# printer_control.net
KiCad netlist of a schematic drawn in Altium Designer
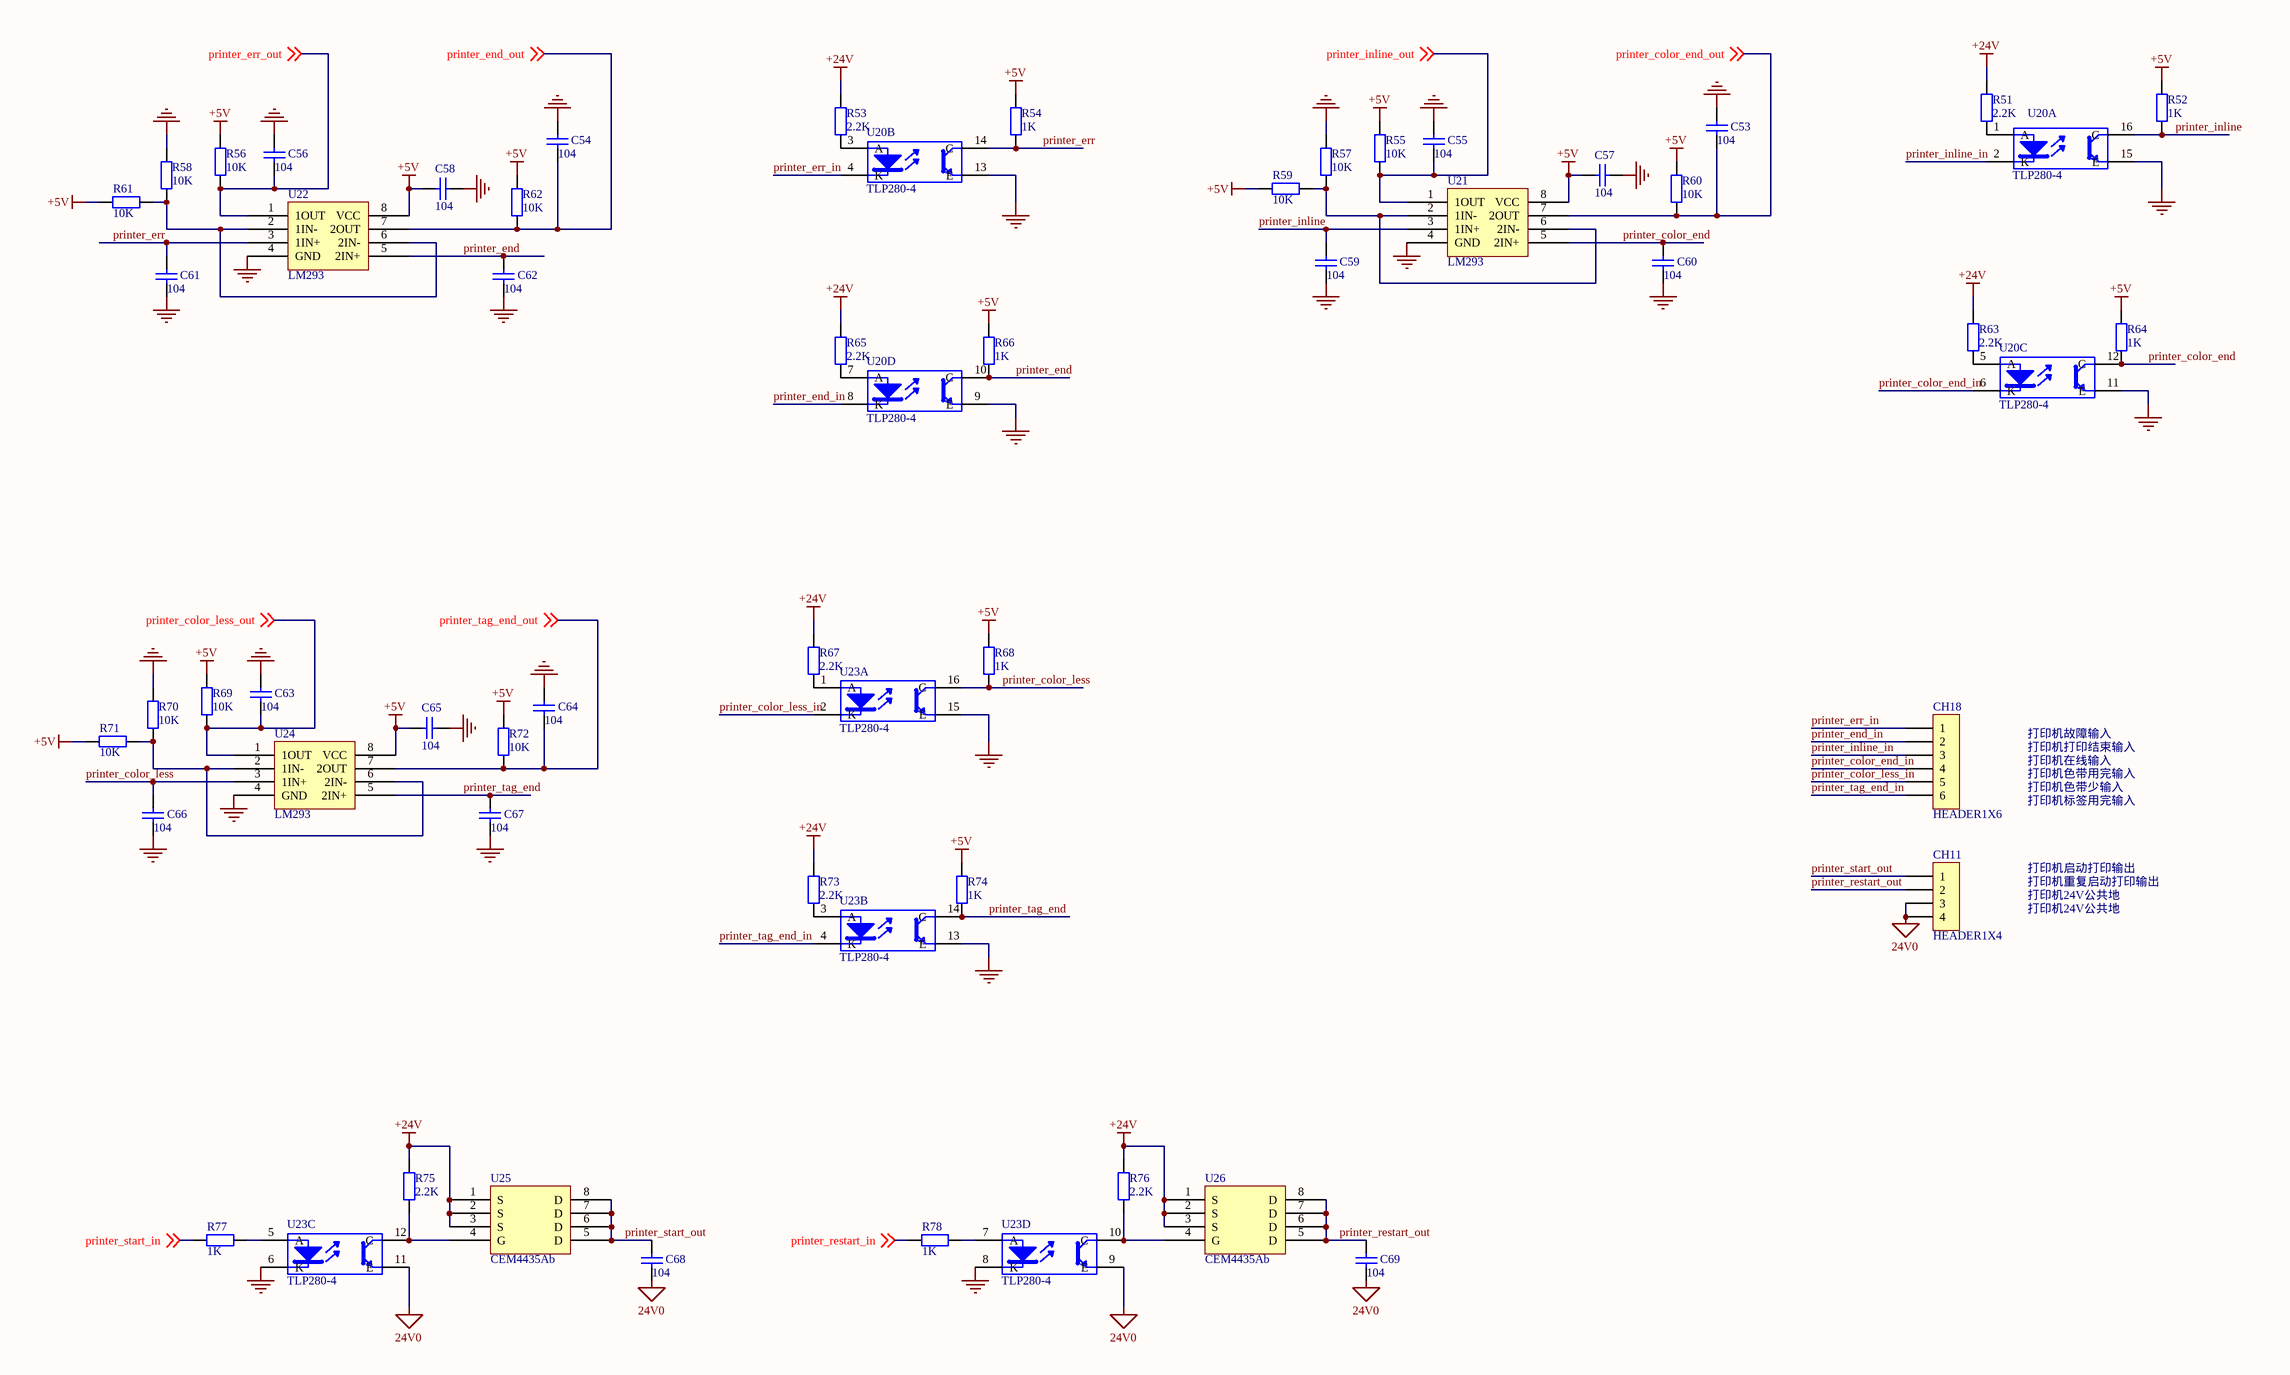
[diagram p0: printer_control.SchDoc]

(export (version "E")
  (design (tool "Eeschema 10.0.6"))
  (components
    (comp (ref "C53")
      (value "104")
      (footprint "0805")
      (description "Capacitor")
      (fields (field (name "Comment") "Cap") (field (name "PUBLISHER") "Altium Limited"))
      (libsource (lib "Miscellaneous Devices") (part "Cap"))
    )
    (comp (ref "C54")
      (value "104")
      (footprint "0805")
      (description "Capacitor")
      (fields (field (name "Comment") "Cap") (field (name "PUBLISHER") "Altium Limited"))
      (libsource (lib "Miscellaneous Devices") (part "Cap"))
    )
    (comp (ref "C55")
      (value "104")
      (footprint "0805")
      (description "Capacitor")
      (fields (field (name "Comment") "Cap") (field (name "PUBLISHER") "Altium Limited"))
      (libsource (lib "Miscellaneous Devices") (part "Cap"))
    )
    (comp (ref "C56")
      (value "104")
      (footprint "0805")
      (description "Capacitor")
      (fields (field (name "Comment") "Cap") (field (name "PUBLISHER") "Altium Limited"))
      (libsource (lib "Miscellaneous Devices") (part "Cap"))
    )
    (comp (ref "C57")
      (value "104")
      (footprint "0805")
      (description "Capacitor")
      (fields (field (name "Comment") "Cap") (field (name "PUBLISHER") "Altium Limited"))
      (libsource (lib "Miscellaneous Devices") (part "Cap"))
    )
    (comp (ref "C58")
      (value "104")
      (footprint "0805")
      (description "Capacitor")
      (fields (field (name "Comment") "Cap") (field (name "PUBLISHER") "Altium Limited"))
      (libsource (lib "Miscellaneous Devices") (part "Cap"))
    )
    (comp (ref "C59")
      (value "104")
      (footprint "0805")
      (description "Capacitor")
      (fields (field (name "Comment") "Cap") (field (name "PUBLISHER") "Altium Limited"))
      (libsource (lib "Miscellaneous Devices") (part "Cap"))
    )
    (comp (ref "C60")
      (value "104")
      (footprint "0805")
      (description "Capacitor")
      (fields (field (name "Comment") "Cap") (field (name "PUBLISHER") "Altium Limited"))
      (libsource (lib "Miscellaneous Devices") (part "Cap"))
    )
    (comp (ref "C61")
      (value "104")
      (footprint "0805")
      (description "Capacitor")
      (fields (field (name "Comment") "Cap") (field (name "PUBLISHER") "Altium Limited"))
      (libsource (lib "Miscellaneous Devices") (part "Cap"))
    )
    (comp (ref "C62")
      (value "104")
      (footprint "0805")
      (description "Capacitor")
      (fields (field (name "Comment") "Cap") (field (name "PUBLISHER") "Altium Limited"))
      (libsource (lib "Miscellaneous Devices") (part "Cap"))
    )
    (comp (ref "C63")
      (value "104")
      (footprint "0805")
      (description "Capacitor")
      (fields (field (name "Comment") "Cap") (field (name "PUBLISHER") "Altium Limited"))
      (libsource (lib "Miscellaneous Devices") (part "Cap"))
    )
    (comp (ref "C64")
      (value "104")
      (footprint "0805")
      (description "Capacitor")
      (fields (field (name "Comment") "Cap") (field (name "PUBLISHER") "Altium Limited"))
      (libsource (lib "Miscellaneous Devices") (part "Cap"))
    )
    (comp (ref "C65")
      (value "104")
      (footprint "0805")
      (description "Capacitor")
      (fields (field (name "Comment") "Cap") (field (name "PUBLISHER") "Altium Limited"))
      (libsource (lib "Miscellaneous Devices") (part "Cap"))
    )
    (comp (ref "C66")
      (value "104")
      (footprint "0805")
      (description "Capacitor")
      (fields (field (name "Comment") "Cap") (field (name "PUBLISHER") "Altium Limited"))
      (libsource (lib "Miscellaneous Devices") (part "Cap"))
    )
    (comp (ref "C67")
      (value "104")
      (footprint "0805")
      (description "Capacitor")
      (fields (field (name "Comment") "Cap") (field (name "PUBLISHER") "Altium Limited"))
      (libsource (lib "Miscellaneous Devices") (part "Cap"))
    )
    (comp (ref "C68")
      (value "104")
      (footprint "0805")
      (description "Capacitor")
      (fields (field (name "Comment") "Capb") (field (name "PUBLISHER") "Altium Limited"))
      (libsource (lib "Miscellaneous Devices") (part "Cap"))
    )
    (comp (ref "C69")
      (value "104")
      (footprint "0805")
      (description "Capacitor")
      (fields (field (name "Comment") "Capb") (field (name "PUBLISHER") "Altium Limited"))
      (libsource (lib "Miscellaneous Devices") (part "Cap"))
    )
    (comp (ref "CH11")
      (value "HEADER1X4")
      (footprint "CH3.96-4PIN")
      (libsource (lib "myIntegrated_Library1") (part "HEADER1X4"))
    )
    (comp (ref "CH18")
      (value "HEADER1X6")
      (footprint "CH3.96-6PIN")
      (libsource (lib "myIntegrated_Library1") (part "HEADER1X6"))
    )
    (comp (ref "R51")
      (value "2.2K")
      (footprint "0805")
      (description "Resistor")
      (fields (field (name "Comment") "Res2") (field (name "PUBLISHER") "Altium Limited"))
      (libsource (lib "") (part "Res2_1"))
    )
    (comp (ref "R52")
      (value "1K")
      (footprint "0805")
      (description "Resistor")
      (fields (field (name "Comment") "Res2") (field (name "PUBLISHER") "Altium Limited"))
      (libsource (lib "") (part "Res2_1"))
    )
    (comp (ref "R53")
      (value "2.2K")
      (footprint "0805")
      (description "Resistor")
      (fields (field (name "Comment") "Res2") (field (name "PUBLISHER") "Altium Limited"))
      (libsource (lib "") (part "Res2_1"))
    )
    (comp (ref "R54")
      (value "1K")
      (footprint "0805")
      (description "Resistor")
      (fields (field (name "Comment") "Res2") (field (name "PUBLISHER") "Altium Limited"))
      (libsource (lib "") (part "Res2_1"))
    )
    (comp (ref "R55")
      (value "10K")
      (footprint "0805")
      (description "Resistor")
      (fields (field (name "Comment") "Res2") (field (name "PUBLISHER") "Altium Limited"))
      (libsource (lib "") (part "Res2_1"))
    )
    (comp (ref "R56")
      (value "10K")
      (footprint "0805")
      (description "Resistor")
      (fields (field (name "Comment") "Res2") (field (name "PUBLISHER") "Altium Limited"))
      (libsource (lib "") (part "Res2_1"))
    )
    (comp (ref "R57")
      (value "10K")
      (footprint "0805")
      (description "Resistor")
      (fields (field (name "Comment") "Res2") (field (name "PUBLISHER") "Altium Limited"))
      (libsource (lib "") (part "Res2_1"))
    )
    (comp (ref "R58")
      (value "10K")
      (footprint "0805")
      (description "Resistor")
      (fields (field (name "Comment") "Res2") (field (name "PUBLISHER") "Altium Limited"))
      (libsource (lib "") (part "Res2_1"))
    )
    (comp (ref "R59")
      (value "10K")
      (footprint "0805")
      (description "Resistor")
      (fields (field (name "Comment") "Res2") (field (name "PUBLISHER") "Altium Limited"))
      (libsource (lib "Miscellaneous Devices") (part "Res2"))
    )
    (comp (ref "R60")
      (value "10K")
      (footprint "0805")
      (description "Resistor")
      (fields (field (name "Comment") "Res2") (field (name "PUBLISHER") "Altium Limited"))
      (libsource (lib "") (part "Res2_1"))
    )
    (comp (ref "R61")
      (value "10K")
      (footprint "0805")
      (description "Resistor")
      (fields (field (name "Comment") "Res2") (field (name "PUBLISHER") "Altium Limited"))
      (libsource (lib "Miscellaneous Devices") (part "Res2"))
    )
    (comp (ref "R62")
      (value "10K")
      (footprint "0805")
      (description "Resistor")
      (fields (field (name "Comment") "Res2") (field (name "PUBLISHER") "Altium Limited"))
      (libsource (lib "") (part "Res2_1"))
    )
    (comp (ref "R63")
      (value "2.2K")
      (footprint "0805")
      (description "Resistor")
      (fields (field (name "Comment") "Res2") (field (name "PUBLISHER") "Altium Limited"))
      (libsource (lib "") (part "Res2_1"))
    )
    (comp (ref "R64")
      (value "1K")
      (footprint "0805")
      (description "Resistor")
      (fields (field (name "Comment") "Res2") (field (name "PUBLISHER") "Altium Limited"))
      (libsource (lib "") (part "Res2_1"))
    )
    (comp (ref "R65")
      (value "2.2K")
      (footprint "0805")
      (description "Resistor")
      (fields (field (name "Comment") "Res2") (field (name "PUBLISHER") "Altium Limited"))
      (libsource (lib "") (part "Res2_1"))
    )
    (comp (ref "R66")
      (value "1K")
      (footprint "0805")
      (description "Resistor")
      (fields (field (name "Comment") "Res2") (field (name "PUBLISHER") "Altium Limited"))
      (libsource (lib "") (part "Res2_1"))
    )
    (comp (ref "R67")
      (value "2.2K")
      (footprint "0805")
      (description "Resistor")
      (fields (field (name "Comment") "Res2") (field (name "PUBLISHER") "Altium Limited"))
      (libsource (lib "") (part "Res2_1"))
    )
    (comp (ref "R68")
      (value "1K")
      (footprint "0805")
      (description "Resistor")
      (fields (field (name "Comment") "Res2") (field (name "PUBLISHER") "Altium Limited"))
      (libsource (lib "") (part "Res2_1"))
    )
    (comp (ref "R69")
      (value "10K")
      (footprint "0805")
      (description "Resistor")
      (fields (field (name "Comment") "Res2") (field (name "PUBLISHER") "Altium Limited"))
      (libsource (lib "") (part "Res2_1"))
    )
    (comp (ref "R70")
      (value "10K")
      (footprint "0805")
      (description "Resistor")
      (fields (field (name "Comment") "Res2") (field (name "PUBLISHER") "Altium Limited"))
      (libsource (lib "") (part "Res2_1"))
    )
    (comp (ref "R71")
      (value "10K")
      (footprint "0805")
      (description "Resistor")
      (fields (field (name "Comment") "Res2") (field (name "PUBLISHER") "Altium Limited"))
      (libsource (lib "Miscellaneous Devices") (part "Res2"))
    )
    (comp (ref "R72")
      (value "10K")
      (footprint "0805")
      (description "Resistor")
      (fields (field (name "Comment") "Res2") (field (name "PUBLISHER") "Altium Limited"))
      (libsource (lib "") (part "Res2_1"))
    )
    (comp (ref "R73")
      (value "2.2K")
      (footprint "0805")
      (description "Resistor")
      (fields (field (name "Comment") "Res2") (field (name "PUBLISHER") "Altium Limited"))
      (libsource (lib "") (part "Res2_1"))
    )
    (comp (ref "R74")
      (value "1K")
      (footprint "0805")
      (description "Resistor")
      (fields (field (name "Comment") "Res2") (field (name "PUBLISHER") "Altium Limited"))
      (libsource (lib "") (part "Res2_1"))
    )
    (comp (ref "R75")
      (value "2.2K")
      (footprint "0805")
      (description "Resistor")
      (fields (field (name "Comment") "Res2") (field (name "PUBLISHER") "Altium Limited"))
      (libsource (lib "") (part "Res2_1"))
    )
    (comp (ref "R76")
      (value "2.2K")
      (footprint "0805")
      (description "Resistor")
      (fields (field (name "Comment") "Res2") (field (name "PUBLISHER") "Altium Limited"))
      (libsource (lib "") (part "Res2_1"))
    )
    (comp (ref "R77")
      (value "1K")
      (footprint "0805")
      (description "Resistor")
      (fields (field (name "Comment") "Res2") (field (name "PUBLISHER") "Altium Limited"))
      (libsource (lib "Miscellaneous Devices") (part "Res2"))
    )
    (comp (ref "R78")
      (value "1K")
      (footprint "0805")
      (description "Resistor")
      (fields (field (name "Comment") "Res2") (field (name "PUBLISHER") "Altium Limited"))
      (libsource (lib "Miscellaneous Devices") (part "Res2"))
    )
    (comp (ref "U20") (value "TLP280-4") (footprint "SO16") (libsource (lib "WH V20") (part "TLP521-4")))
    (comp (ref "U21")
      (value "LM293")
      (footprint "SOP8-OP27")
      (libsource (lib "myIntegrated_Library1") (part "LM293"))
    )
    (comp (ref "U22")
      (value "LM293")
      (footprint "SOP8-OP27")
      (libsource (lib "myIntegrated_Library1") (part "LM293"))
    )
    (comp (ref "U23") (value "TLP280-4") (footprint "SO16") (libsource (lib "WH V20") (part "TLP521-4")))
    (comp (ref "U24")
      (value "LM293")
      (footprint "SOP8-OP27")
      (libsource (lib "myIntegrated_Library1") (part "LM293"))
    )
    (comp (ref "U25")
      (value "CEM4435Ab")
      (footprint "SOP8-OP27")
      (libsource (lib "myIntegrated_Library1") (part "CEM4435A"))
    )
    (comp (ref "U26")
      (value "CEM4435Ab")
      (footprint "SOP8-OP27")
      (libsource (lib "myIntegrated_Library1") (part "CEM4435A"))
    )
  )
  (nets
    (net (code "1") (name "+5V") (class "Default")
      (node (ref "C57") (pin "2") (pinfunction "2_2") (pintype "passive"))
      (node (ref "C58") (pin "2") (pinfunction "2_2") (pintype "passive"))
      (node (ref "C65") (pin "2") (pinfunction "2_2") (pintype "passive"))
      (node (ref "R52") (pin "1") (pinfunction "1_1") (pintype "passive"))
      (node (ref "R54") (pin "1") (pinfunction "1_1") (pintype "passive"))
      (node (ref "R55") (pin "1") (pinfunction "1_1") (pintype "passive"))
      (node (ref "R56") (pin "1") (pinfunction "1_1") (pintype "passive"))
      (node (ref "R59") (pin "1") (pinfunction "1_1") (pintype "passive"))
      (node (ref "R60") (pin "1") (pinfunction "1_1") (pintype "passive"))
      (node (ref "R61") (pin "1") (pinfunction "1_1") (pintype "passive"))
      (node (ref "R62") (pin "1") (pinfunction "1_1") (pintype "passive"))
      (node (ref "R64") (pin "1") (pinfunction "1_1") (pintype "passive"))
      (node (ref "R66") (pin "1") (pinfunction "1_1") (pintype "passive"))
      (node (ref "R68") (pin "1") (pinfunction "1_1") (pintype "passive"))
      (node (ref "R69") (pin "1") (pinfunction "1_1") (pintype "passive"))
      (node (ref "R71") (pin "1") (pinfunction "1_1") (pintype "passive"))
      (node (ref "R72") (pin "1") (pinfunction "1_1") (pintype "passive"))
      (node (ref "R74") (pin "1") (pinfunction "1_1") (pintype "passive"))
      (node (ref "U21") (pin "8") (pinfunction "VCC_8") (pintype "passive"))
      (node (ref "U22") (pin "8") (pinfunction "VCC_8") (pintype "passive"))
      (node (ref "U24") (pin "8") (pinfunction "VCC_8") (pintype "passive"))
    )
    (net (code "2") (name "+24V") (class "Default")
      (node (ref "R51") (pin "1") (pinfunction "1_1") (pintype "passive"))
      (node (ref "R53") (pin "1") (pinfunction "1_1") (pintype "passive"))
      (node (ref "R63") (pin "1") (pinfunction "1_1") (pintype "passive"))
      (node (ref "R65") (pin "1") (pinfunction "1_1") (pintype "passive"))
      (node (ref "R67") (pin "1") (pinfunction "1_1") (pintype "passive"))
      (node (ref "R73") (pin "1") (pinfunction "1_1") (pintype "passive"))
      (node (ref "R75") (pin "1") (pinfunction "1_1") (pintype "passive"))
      (node (ref "R76") (pin "1") (pinfunction "1_1") (pintype "passive"))
      (node (ref "U25") (pin "1") (pinfunction "S_1") (pintype "passive"))
      (node (ref "U25") (pin "2") (pinfunction "S_2") (pintype "passive"))
      (node (ref "U25") (pin "3") (pinfunction "S_3") (pintype "passive"))
      (node (ref "U26") (pin "1") (pinfunction "S_1") (pintype "passive"))
      (node (ref "U26") (pin "2") (pinfunction "S_2") (pintype "passive"))
      (node (ref "U26") (pin "3") (pinfunction "S_3") (pintype "passive"))
    )
    (net (code "3") (name "/printer_color_end") (class "Default")
      (node (ref "C60") (pin "2") (pinfunction "2_2") (pintype "passive"))
      (node (ref "R64") (pin "2") (pinfunction "2_2") (pintype "passive"))
      (node (ref "U20") (pin "12") (pinfunction "C_12") (pintype "passive"))
      (node (ref "U21") (pin "5") (pinfunction "2IN+_5") (pintype "passive"))
    )
    (net (code "4") (name "/printer_color_end_in") (class "Default")
      (node (ref "CH18") (pin "4") (pinfunction "4_4") (pintype "passive"))
      (node (ref "U20") (pin "6") (pinfunction "K_6") (pintype "passive"))
    )
    (net (code "5") (name "/printer_color_less") (class "Default")
      (node (ref "C66") (pin "2") (pinfunction "2_2") (pintype "passive"))
      (node (ref "R68") (pin "2") (pinfunction "2_2") (pintype "passive"))
      (node (ref "U23") (pin "16") (pinfunction "C_16") (pintype "passive"))
      (node (ref "U24") (pin "3") (pinfunction "1IN+_3") (pintype "passive"))
    )
    (net (code "6") (name "/printer_color_less_in") (class "Default")
      (node (ref "CH18") (pin "5") (pinfunction "5_5") (pintype "passive"))
      (node (ref "U23") (pin "2") (pinfunction "K_2") (pintype "passive"))
    )
    (net (code "7") (name "/printer_end") (class "Default")
      (node (ref "C62") (pin "2") (pinfunction "2_2") (pintype "passive"))
      (node (ref "R66") (pin "2") (pinfunction "2_2") (pintype "passive"))
      (node (ref "U20") (pin "10") (pinfunction "C_10") (pintype "passive"))
      (node (ref "U22") (pin "5") (pinfunction "2IN+_5") (pintype "passive"))
    )
    (net (code "8") (name "/printer_end_in") (class "Default")
      (node (ref "CH18") (pin "2") (pinfunction "2_2") (pintype "passive"))
      (node (ref "U20") (pin "8") (pinfunction "K_8") (pintype "passive"))
    )
    (net (code "9") (name "/printer_err") (class "Default")
      (node (ref "C61") (pin "2") (pinfunction "2_2") (pintype "passive"))
      (node (ref "R54") (pin "2") (pinfunction "2_2") (pintype "passive"))
      (node (ref "U20") (pin "14") (pinfunction "C_14") (pintype "passive"))
      (node (ref "U22") (pin "3") (pinfunction "1IN+_3") (pintype "passive"))
    )
    (net (code "10") (name "/printer_err_in") (class "Default")
      (node (ref "CH18") (pin "1") (pinfunction "1_1") (pintype "passive"))
      (node (ref "U20") (pin "4") (pinfunction "K_4") (pintype "passive"))
    )
    (net (code "11") (name "/printer_inline") (class "Default")
      (node (ref "C59") (pin "2") (pinfunction "2_2") (pintype "passive"))
      (node (ref "R52") (pin "2") (pinfunction "2_2") (pintype "passive"))
      (node (ref "U20") (pin "16") (pinfunction "C_16") (pintype "passive"))
      (node (ref "U21") (pin "3") (pinfunction "1IN+_3") (pintype "passive"))
    )
    (net (code "12") (name "/printer_inline_in") (class "Default")
      (node (ref "CH18") (pin "3") (pinfunction "3_3") (pintype "passive"))
      (node (ref "U20") (pin "2") (pinfunction "K_2") (pintype "passive"))
    )
    (net (code "13") (name "/printer_restart_out") (class "Default")
      (node (ref "C69") (pin "2") (pinfunction "2_2") (pintype "passive"))
      (node (ref "CH11") (pin "2") (pinfunction "2_2") (pintype "passive"))
      (node (ref "U26") (pin "5") (pinfunction "D_5") (pintype "passive"))
      (node (ref "U26") (pin "6") (pinfunction "D_6") (pintype "passive"))
      (node (ref "U26") (pin "7") (pinfunction "D_7") (pintype "passive"))
      (node (ref "U26") (pin "8") (pinfunction "D_8") (pintype "passive"))
    )
    (net (code "14") (name "/printer_start_out") (class "Default")
      (node (ref "C68") (pin "2") (pinfunction "2_2") (pintype "passive"))
      (node (ref "CH11") (pin "1") (pinfunction "1_1") (pintype "passive"))
      (node (ref "U25") (pin "5") (pinfunction "D_5") (pintype "passive"))
      (node (ref "U25") (pin "6") (pinfunction "D_6") (pintype "passive"))
      (node (ref "U25") (pin "7") (pinfunction "D_7") (pintype "passive"))
      (node (ref "U25") (pin "8") (pinfunction "D_8") (pintype "passive"))
    )
    (net (code "15") (name "/printer_tag_end") (class "Default")
      (node (ref "C67") (pin "2") (pinfunction "2_2") (pintype "passive"))
      (node (ref "R74") (pin "2") (pinfunction "2_2") (pintype "passive"))
      (node (ref "U23") (pin "14") (pinfunction "C_14") (pintype "passive"))
      (node (ref "U24") (pin "5") (pinfunction "2IN+_5") (pintype "passive"))
    )
    (net (code "16") (name "/printer_tag_end_in") (class "Default")
      (node (ref "CH18") (pin "6") (pinfunction "6_6") (pintype "passive"))
      (node (ref "U23") (pin "4") (pinfunction "K_4") (pintype "passive"))
    )
    (net (code "17") (name "24V0") (class "Default")
      (node (ref "C68") (pin "1") (pinfunction "1_1") (pintype "passive"))
      (node (ref "C69") (pin "1") (pinfunction "1_1") (pintype "passive"))
      (node (ref "CH11") (pin "3") (pinfunction "3_3") (pintype "passive"))
      (node (ref "CH11") (pin "4") (pinfunction "4_4") (pintype "passive"))
      (node (ref "U23") (pin "11") (pinfunction "E_11") (pintype "passive"))
      (node (ref "U23") (pin "9") (pinfunction "E_9") (pintype "passive"))
    )
    (net (code "18") (name "GND") (class "Default")
      (node (ref "C53") (pin "2") (pinfunction "2_2") (pintype "passive"))
      (node (ref "C54") (pin "2") (pinfunction "2_2") (pintype "passive"))
      (node (ref "C55") (pin "2") (pinfunction "2_2") (pintype "passive"))
      (node (ref "C56") (pin "2") (pinfunction "2_2") (pintype "passive"))
      (node (ref "C57") (pin "1") (pinfunction "1_1") (pintype "passive"))
      (node (ref "C58") (pin "1") (pinfunction "1_1") (pintype "passive"))
      (node (ref "C59") (pin "1") (pinfunction "1_1") (pintype "passive"))
      (node (ref "C60") (pin "1") (pinfunction "1_1") (pintype "passive"))
      (node (ref "C61") (pin "1") (pinfunction "1_1") (pintype "passive"))
      (node (ref "C62") (pin "1") (pinfunction "1_1") (pintype "passive"))
      (node (ref "C63") (pin "2") (pinfunction "2_2") (pintype "passive"))
      (node (ref "C64") (pin "2") (pinfunction "2_2") (pintype "passive"))
      (node (ref "C65") (pin "1") (pinfunction "1_1") (pintype "passive"))
      (node (ref "C66") (pin "1") (pinfunction "1_1") (pintype "passive"))
      (node (ref "C67") (pin "1") (pinfunction "1_1") (pintype "passive"))
      (node (ref "R57") (pin "1") (pinfunction "1_1") (pintype "passive"))
      (node (ref "R58") (pin "1") (pinfunction "1_1") (pintype "passive"))
      (node (ref "R70") (pin "1") (pinfunction "1_1") (pintype "passive"))
      (node (ref "U20") (pin "11") (pinfunction "E_11") (pintype "passive"))
      (node (ref "U20") (pin "13") (pinfunction "E_13") (pintype "passive"))
      (node (ref "U20") (pin "15") (pinfunction "E_15") (pintype "passive"))
      (node (ref "U20") (pin "9") (pinfunction "E_9") (pintype "passive"))
      (node (ref "U21") (pin "4") (pinfunction "GND_4") (pintype "passive"))
      (node (ref "U22") (pin "4") (pinfunction "GND_4") (pintype "passive"))
      (node (ref "U23") (pin "13") (pinfunction "E_13") (pintype "passive"))
      (node (ref "U23") (pin "15") (pinfunction "E_15") (pintype "passive"))
      (node (ref "U23") (pin "6") (pinfunction "K_6") (pintype "passive"))
      (node (ref "U23") (pin "8") (pinfunction "K_8") (pintype "passive"))
      (node (ref "U24") (pin "4") (pinfunction "GND_4") (pintype "passive"))
    )
    (net (code "19") (name "Net-(U20A-A)") (class "Default")
      (node (ref "R51") (pin "2") (pinfunction "2_2") (pintype "passive"))
      (node (ref "U20") (pin "1") (pinfunction "A_1") (pintype "passive"))
    )
    (net (code "20") (name "Net-(U20B-A)") (class "Default")
      (node (ref "R53") (pin "2") (pinfunction "2_2") (pintype "passive"))
      (node (ref "U20") (pin "3") (pinfunction "A_3") (pintype "passive"))
    )
    (net (code "21") (name "Net-(U20C-A)") (class "Default")
      (node (ref "R63") (pin "2") (pinfunction "2_2") (pintype "passive"))
      (node (ref "U20") (pin "5") (pinfunction "A_5") (pintype "passive"))
    )
    (net (code "22") (name "Net-(U20D-A)") (class "Default")
      (node (ref "R65") (pin "2") (pinfunction "2_2") (pintype "passive"))
      (node (ref "U20") (pin "7") (pinfunction "A_7") (pintype "passive"))
    )
    (net (code "23") (name "Net-(U21-1IN-)") (class "Default")
      (node (ref "R57") (pin "2") (pinfunction "2_2") (pintype "passive"))
      (node (ref "R59") (pin "2") (pinfunction "2_2") (pintype "passive"))
      (node (ref "U21") (pin "2") (pinfunction "1IN-_2") (pintype "passive"))
      (node (ref "U21") (pin "6") (pinfunction "2IN-_6") (pintype "passive"))
    )
    (net (code "24") (name "Net-(U22-1IN-)") (class "Default")
      (node (ref "R58") (pin "2") (pinfunction "2_2") (pintype "passive"))
      (node (ref "R61") (pin "2") (pinfunction "2_2") (pintype "passive"))
      (node (ref "U22") (pin "2") (pinfunction "1IN-_2") (pintype "passive"))
      (node (ref "U22") (pin "6") (pinfunction "2IN-_6") (pintype "passive"))
    )
    (net (code "25") (name "Net-(U23A-A)") (class "Default")
      (node (ref "R67") (pin "2") (pinfunction "2_2") (pintype "passive"))
      (node (ref "U23") (pin "1") (pinfunction "A_1") (pintype "passive"))
    )
    (net (code "26") (name "Net-(U23B-A)") (class "Default")
      (node (ref "R73") (pin "2") (pinfunction "2_2") (pintype "passive"))
      (node (ref "U23") (pin "3") (pinfunction "A_3") (pintype "passive"))
    )
    (net (code "27") (name "Net-(U23C-A)") (class "Default")
      (node (ref "R77") (pin "2") (pinfunction "2_2") (pintype "passive"))
      (node (ref "U23") (pin "5") (pinfunction "A_5") (pintype "passive"))
    )
    (net (code "28") (name "Net-(U23C-C)") (class "Default")
      (node (ref "R75") (pin "2") (pinfunction "2_2") (pintype "passive"))
      (node (ref "U23") (pin "12") (pinfunction "C_12") (pintype "passive"))
      (node (ref "U25") (pin "4") (pinfunction "G_4") (pintype "passive"))
    )
    (net (code "29") (name "Net-(U23D-A)") (class "Default")
      (node (ref "R78") (pin "2") (pinfunction "2_2") (pintype "passive"))
      (node (ref "U23") (pin "7") (pinfunction "A_7") (pintype "passive"))
    )
    (net (code "30") (name "Net-(U23D-C)") (class "Default")
      (node (ref "R76") (pin "2") (pinfunction "2_2") (pintype "passive"))
      (node (ref "U23") (pin "10") (pinfunction "C_10") (pintype "passive"))
      (node (ref "U26") (pin "4") (pinfunction "G_4") (pintype "passive"))
    )
    (net (code "31") (name "Net-(U24-1IN-)") (class "Default")
      (node (ref "R70") (pin "2") (pinfunction "2_2") (pintype "passive"))
      (node (ref "R71") (pin "2") (pinfunction "2_2") (pintype "passive"))
      (node (ref "U24") (pin "2") (pinfunction "1IN-_2") (pintype "passive"))
      (node (ref "U24") (pin "6") (pinfunction "2IN-_6") (pintype "passive"))
    )
    (net (code "32") (name "printer_color_end_out") (class "Default")
      (node (ref "C53") (pin "1") (pinfunction "1_1") (pintype "passive"))
      (node (ref "R60") (pin "2") (pinfunction "2_2") (pintype "passive"))
      (node (ref "U21") (pin "7") (pinfunction "2OUT_7") (pintype "passive"))
    )
    (net (code "33") (name "printer_color_less_out") (class "Default")
      (node (ref "C63") (pin "1") (pinfunction "1_1") (pintype "passive"))
      (node (ref "R69") (pin "2") (pinfunction "2_2") (pintype "passive"))
      (node (ref "U24") (pin "1") (pinfunction "1OUT_1") (pintype "passive"))
    )
    (net (code "34") (name "printer_end_out") (class "Default")
      (node (ref "C54") (pin "1") (pinfunction "1_1") (pintype "passive"))
      (node (ref "R62") (pin "2") (pinfunction "2_2") (pintype "passive"))
      (node (ref "U22") (pin "7") (pinfunction "2OUT_7") (pintype "passive"))
    )
    (net (code "35") (name "printer_err_out") (class "Default")
      (node (ref "C56") (pin "1") (pinfunction "1_1") (pintype "passive"))
      (node (ref "R56") (pin "2") (pinfunction "2_2") (pintype "passive"))
      (node (ref "U22") (pin "1") (pinfunction "1OUT_1") (pintype "passive"))
    )
    (net (code "36") (name "printer_inline_out") (class "Default")
      (node (ref "C55") (pin "1") (pinfunction "1_1") (pintype "passive"))
      (node (ref "R55") (pin "2") (pinfunction "2_2") (pintype "passive"))
      (node (ref "U21") (pin "1") (pinfunction "1OUT_1") (pintype "passive"))
    )
    (net (code "37") (name "printer_restart_in") (class "Default")
      (node (ref "R78") (pin "1") (pinfunction "1_1") (pintype "passive"))
    )
    (net (code "38") (name "printer_start_in") (class "Default")
      (node (ref "R77") (pin "1") (pinfunction "1_1") (pintype "passive"))
    )
    (net (code "39") (name "printer_tag_end_out") (class "Default")
      (node (ref "C64") (pin "1") (pinfunction "1_1") (pintype "passive"))
      (node (ref "R72") (pin "2") (pinfunction "2_2") (pintype "passive"))
      (node (ref "U24") (pin "7") (pinfunction "2OUT_7") (pintype "passive"))
    )
  )
)
